# SH4_-_17V_BUCK_CONVERTER.net
KiCad netlist of a schematic drawn in Altium Designer
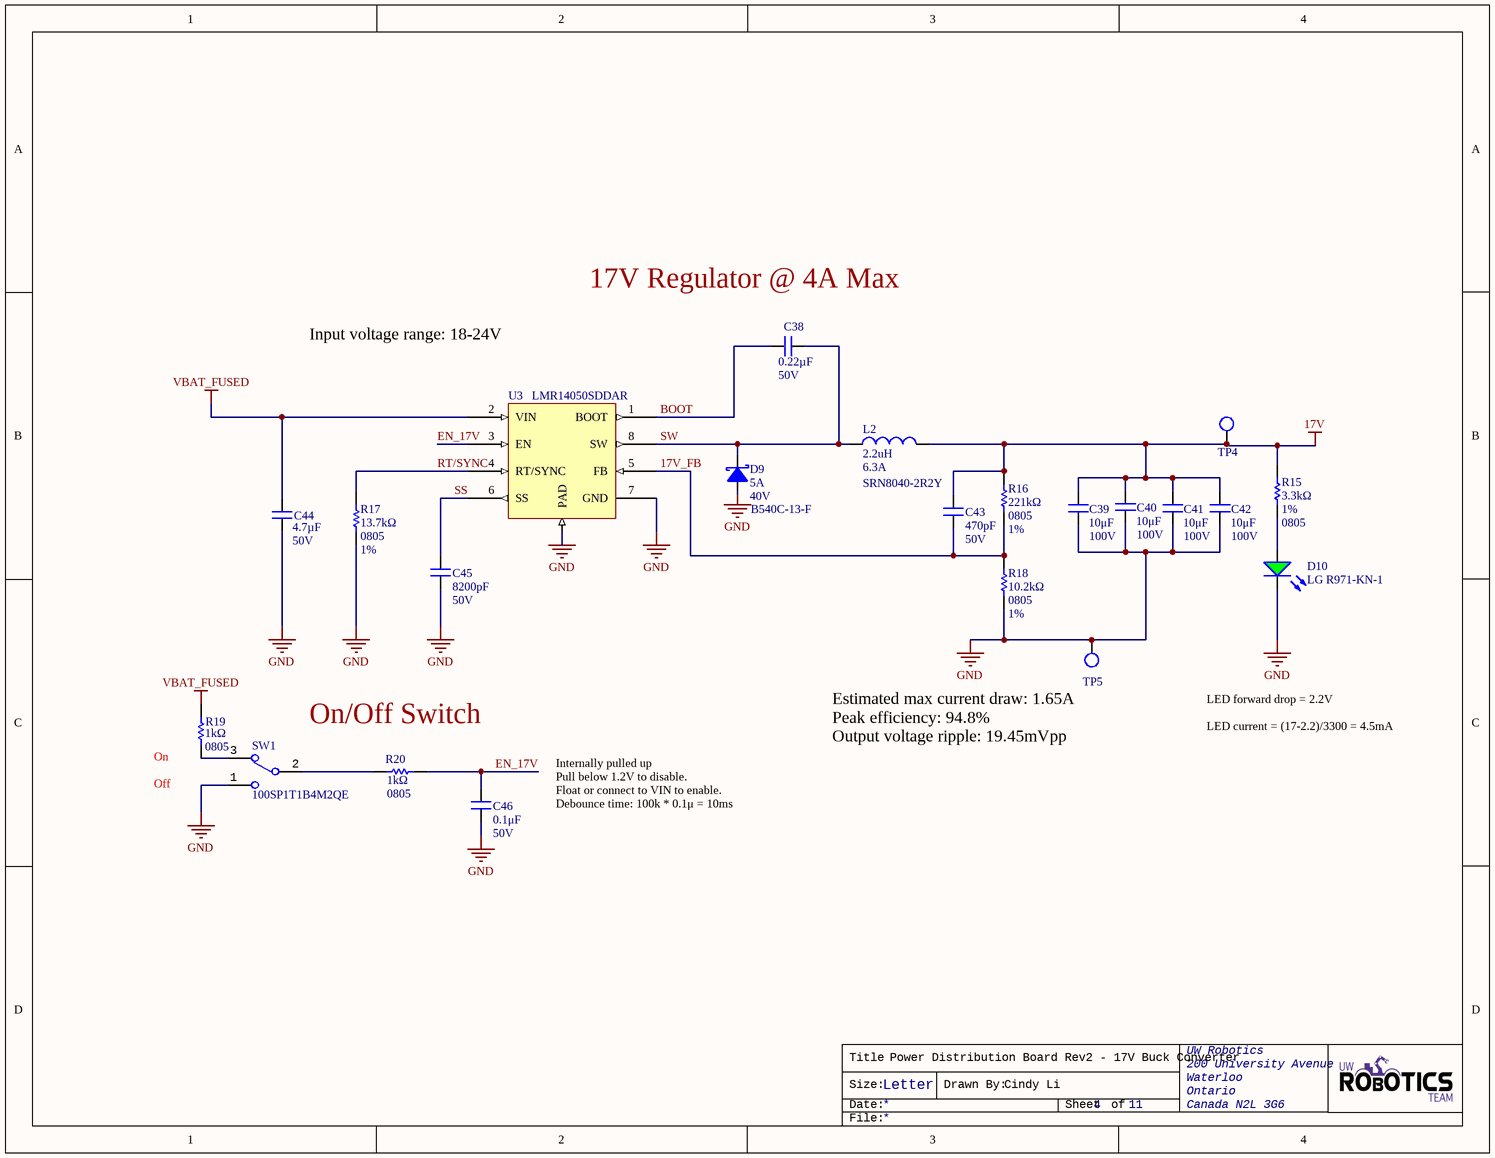
[diagram p0: SH4 - 17V BUCK CONVERTER.SchDoc]

(export (version "E")
  (design (tool "Eeschema 10.0.6"))
  (components
    (comp (ref "C38")
      (value "GRM21BR71H224MA01L")
      (footprint "CAP2012")
      (description "CAP CER 0.22UF 50V X7R 0805")
      (fields
        (field (name "TOLERANCE") "20%")
        (field (name "VOLTAGE RATING") "50V")
        (field (name "CAPACITANCE") "0.22µF")
      )
      (libsource (lib "UWRT_Schematic_Library_2020") (part "GRM21BR71H224MA01L"))
    )
    (comp (ref "C39")
      (value "10μF")
      (footprint "CAP1210")
      (description "CAP CER 10uF 100V X7S 10% 1210")
      (fields
        (field (name "TOLERANCE") "10%")
        (field (name "VOLTAGE RATING") "100V")
        (field (name "Comment") "CAP_10uF_100V_1210")
      )
      (libsource (lib "UWRT_Schematic_Library_2020") (part "CAP_10uF_100V_1210"))
    )
    (comp (ref "C40")
      (value "10μF")
      (footprint "CAP1210")
      (description "CAP CER 10uF 100V X7S 10% 1210")
      (fields
        (field (name "TOLERANCE") "10%")
        (field (name "VOLTAGE RATING") "100V")
        (field (name "Comment") "CAP_10uF_100V_1210")
      )
      (libsource (lib "UWRT_Schematic_Library_2020") (part "CAP_10uF_100V_1210"))
    )
    (comp (ref "C41")
      (value "10μF")
      (footprint "CAP1210")
      (description "CAP CER 10uF 100V X7S 10% 1210")
      (fields
        (field (name "TOLERANCE") "10%")
        (field (name "VOLTAGE RATING") "100V")
        (field (name "Comment") "CAP_10uF_100V_1210")
      )
      (libsource (lib "UWRT_Schematic_Library_2020") (part "CAP_10uF_100V_1210"))
    )
    (comp (ref "C42")
      (value "10μF")
      (footprint "CAP1210")
      (description "CAP CER 10uF 100V X7S 10% 1210")
      (fields
        (field (name "TOLERANCE") "10%")
        (field (name "VOLTAGE RATING") "100V")
        (field (name "Comment") "CAP_10uF_100V_1210")
      )
      (libsource (lib "UWRT_Schematic_Library_2020") (part "CAP_10uF_100V_1210"))
    )
    (comp (ref "C43")
      (value "470pF")
      (footprint "CAP2012")
      (description "CAP CER 470PF 50V X7R 0805")
      (fields (field (name "VOLTAGE RATING") "50V") (field (name "TOLERANCE") "5%"))
      (libsource (lib "UWRT_Schematic_Library_2020") (part "CAP_470pF_50V_0805"))
    )
    (comp (ref "C44")
      (value "GRM31CR71H475KA12L")
      (footprint "CAP1206")
      (description "CAP CER 4.7UF 50V X7R 1206")
      (fields
        (field (name "TOLERANCE") "10%")
        (field (name "VOLTAGE") "50V")
        (field (name "VOLTAGE RATING") "50V")
        (field (name "CAPACITANCE") "4.7µF")
      )
      (libsource (lib "UWRT_Schematic_Library_2020") (part "GRM31CR71H475KA12L"))
    )
    (comp (ref "C45")
      (value "8200pF")
      (footprint "CAP2012")
      (description "CAP CER 8200PF 50V X7R 0805")
      (fields (field (name "TOLERANCE") "10%") (field (name "VOLTAGE RATING") "50V"))
      (libsource (lib "UWRT_Schematic_Library_2020") (part "CAP_8200pF_50V_0805"))
    )
    (comp (ref "C46")
      (value "0.1μF")
      (footprint "CAP2012")
      (description "CAP CER 0.1UF 50V X7R 0805")
      (fields (field (name "VOLTAGE RATING") "50V") (field (name "TOLERANCE") "10%"))
      (libsource (lib "UWRT_Schematic_Library_2020") (part "CAP_0.1uF_50V_0805"))
    )
    (comp (ref "D9")
      (value "B540C-13-F")
      (footprint "DO214AB SMC")
      (description "DIODE SCHOTTKY 40V 5A SMC")
      (fields
        (field (name "MANUFACTURER PART NUMBER 1") "B540C-13-F")
        (field (name "FORWARD CURRENT") "5A")
        (field (name "VOLTAGE") "40V")
      )
      (libsource (lib "UWRT_Schematic_Library_2020") (part "B540C-13-F"))
    )
    (comp (ref "D10")
      (value "LG R971-KN-1")
      (footprint "LED_0805_GREEN")
      (description "LED GREEN DIFFUSED 0805 SMD")
      (libsource (lib "UWRT_Schematic_Library_2020") (part "DIO_LED_G"))
    )
    (comp (ref "L2")
      (value "SRN8040-2R2Y")
      (footprint "IND_BOURNS_SRN80")
      (description "FIXED IND 2.2UH 6.3A 13 MOHM SMD")
      (fields
        (field (name "MANUFACTURER PART NUMBER 1") "SRN8040-2R2Y")
        (field (name "TOLERANCE") "30%")
        (field (name "INDUCTANCE") "2.2uH")
        (field (name "MAX DC CURRENT") "6.3A")
      )
      (libsource (lib "UWRT_Schematic_Library_2020") (part "SRN8040-2R2Y"))
    )
    (comp (ref "R15")
      (value "3.3kΩ")
      (footprint "RESC2012X60N")
      (description "RES 3.3K OHM 1% 1/8W 0805")
      (fields (field (name "TOLERANCE") "1%") (field (name "CASE CODE (IMPERIAL)") "0805"))
      (libsource (lib "UWRT_Schematic_Library_2020") (part "RES_3.3kΩ_0805_1%"))
    )
    (comp (ref "R16")
      (value "221kΩ")
      (footprint "RESC2012X60N")
      (description "RES 221K OHM 1% 1/8W 0805")
      (fields (field (name "CASE CODE (IMPERIAL)") "0805") (field (name "TOLERANCE") "1%"))
      (libsource (lib "UWRT_Schematic_Library_2020") (part "RES_221kΩ_0805_1%"))
    )
    (comp (ref "R17")
      (value "13.7kΩ")
      (footprint "RESC2012X60N")
      (description "RES 13.7K OHM 1% 1/8W 0805")
      (fields (field (name "CASE CODE (IMPERIAL)") "0805") (field (name "TOLERANCE") "1%"))
      (libsource (lib "UWRT_Schematic_Library_2020") (part "RES_13.7kΩ_0805_1%"))
    )
    (comp (ref "R18")
      (value "10.2kΩ")
      (footprint "RESC2012X60N")
      (description "RES 10.2K OHM 1% 1/8W 0805")
      (fields (field (name "CASE CODE (IMPERIAL)") "0805") (field (name "TOLERANCE") "1%"))
      (libsource (lib "UWRT_Schematic_Library_2020") (part "RES_10.2kΩ_0805_1%"))
    )
    (comp (ref "R19")
      (value "1kΩ")
      (footprint "RESC2012X60N")
      (description "RES 1K OHM 1% 1/8W 0805")
      (fields (field (name "TOLERANCE") "1%") (field (name "CASE CODE (IMPERIAL)") "0805"))
      (libsource (lib "UWRT_Schematic_Library_2020") (part "RES_1kΩ_0805_1%"))
    )
    (comp (ref "R20")
      (value "1kΩ")
      (footprint "RESC2012X60N")
      (description "RES 1K OHM 1% 1/8W 0805")
      (fields (field (name "TOLERANCE") "1%") (field (name "CASE CODE (IMPERIAL)") "0805"))
      (libsource (lib "UWRT_Schematic_Library_2020") (part "RES_1kΩ_0805_1%"))
    )
    (comp (ref "SW1")
      (value "100SP1T1B4M2QE")
      (footprint "100SP1T1B4M2QE")
      (description "SWITCH TOGGLE SPDT 5A 120V")
      (libsource (lib "UWRT_Schematic_Library_2020") (part "SW_SPDT"))
    )
    (comp (ref "TP4")
      (value "TESTPOINT_LOOP")
      (footprint "TESTPOINT_LOOP")
      (description "PC TEST POINT MINIATURE WHITE")
      (libsource (lib "UWRT_Schematic_Library_2020") (part "TESTPOINT_LOOP"))
    )
    (comp (ref "TP5")
      (value "TESTPOINT_LOOP")
      (footprint "TESTPOINT_LOOP")
      (description "PC TEST POINT MINIATURE WHITE")
      (libsource (lib "UWRT_Schematic_Library_2020") (part "TESTPOINT_LOOP"))
    )
    (comp (ref "U3")
      (value "LMR14050SDDAR")
      (footprint "8-PowerSOIC")
      (description "IC REG BUCK ADJUSTABLE 5A 8SOPWR")
      (libsource (lib "UWRT_Schematic_Library_2020") (part "LMR14050SDDAR"))
    )
  )
  (nets
    (net (code "1") (name "/17V_FB") (class "Default")
      (node (ref "C43") (pin "1") (pinfunction "1_1") (pintype "passive"))
      (node (ref "R16") (pin "1") (pinfunction "1_1") (pintype "passive"))
      (node (ref "R18") (pin "2") (pinfunction "2_2") (pintype "passive"))
      (node (ref "U3") (pin "5") (pinfunction "FB_5") (pintype "input"))
    )
    (net (code "2") (name "/BOOT") (class "Default")
      (node (ref "C38") (pin "2") (pinfunction "2_2") (pintype "passive"))
      (node (ref "U3") (pin "1") (pinfunction "BOOT_1") (pintype "output"))
    )
    (net (code "3") (name "/EN_17V") (class "Default")
      (node (ref "C46") (pin "2") (pinfunction "2_2") (pintype "passive"))
      (node (ref "R20") (pin "2") (pinfunction "2_2") (pintype "passive"))
      (node (ref "U3") (pin "3") (pinfunction "EN_3") (pintype "input"))
    )
    (net (code "4") (name "/RT{slash}SYNC") (class "Default")
      (node (ref "R17") (pin "2") (pinfunction "2_2") (pintype "passive"))
      (node (ref "U3") (pin "4") (pinfunction "RT/SYNC_4") (pintype "input"))
    )
    (net (code "5") (name "/SS") (class "Default")
      (node (ref "C45") (pin "2") (pinfunction "2_2") (pintype "passive"))
      (node (ref "U3") (pin "6") (pinfunction "SS_6") (pintype "output"))
    )
    (net (code "6") (name "/SW") (class "Default")
      (node (ref "C38") (pin "1") (pinfunction "1_1") (pintype "passive"))
      (node (ref "D9") (pin "2") (pinfunction "Cathode_2") (pintype "passive"))
      (node (ref "L2") (pin "1") (pinfunction "1_1") (pintype "passive"))
      (node (ref "U3") (pin "8") (pinfunction "SW_8") (pintype "output"))
    )
    (net (code "7") (name "17V") (class "Default")
      (node (ref "C39") (pin "2") (pinfunction "2_2") (pintype "passive"))
      (node (ref "C40") (pin "2") (pinfunction "2_2") (pintype "passive"))
      (node (ref "C41") (pin "2") (pinfunction "2_2") (pintype "passive"))
      (node (ref "C42") (pin "2") (pinfunction "2_2") (pintype "passive"))
      (node (ref "C43") (pin "2") (pinfunction "2_2") (pintype "passive"))
      (node (ref "L2") (pin "2") (pinfunction "2_2") (pintype "passive"))
      (node (ref "R15") (pin "2") (pinfunction "2_2") (pintype "passive"))
      (node (ref "R16") (pin "2") (pinfunction "2_2") (pintype "passive"))
      (node (ref "TP4") (pin "1") (pintype "passive"))
    )
    (net (code "8") (name "GND") (class "Default")
      (node (ref "C39") (pin "1") (pinfunction "1_1") (pintype "passive"))
      (node (ref "C40") (pin "1") (pinfunction "1_1") (pintype "passive"))
      (node (ref "C41") (pin "1") (pinfunction "1_1") (pintype "passive"))
      (node (ref "C42") (pin "1") (pinfunction "1_1") (pintype "passive"))
      (node (ref "C44") (pin "2") (pinfunction "2_2") (pintype "passive"))
      (node (ref "C45") (pin "1") (pinfunction "1_1") (pintype "passive"))
      (node (ref "C46") (pin "1") (pinfunction "1_1") (pintype "passive"))
      (node (ref "D10") (pin "2") (pinfunction "K_2") (pintype "passive"))
      (node (ref "D9") (pin "1") (pinfunction "Anode_1") (pintype "passive"))
      (node (ref "R17") (pin "1") (pinfunction "1_1") (pintype "passive"))
      (node (ref "R18") (pin "1") (pinfunction "1_1") (pintype "passive"))
      (node (ref "SW1") (pin "1") (pinfunction "1_1") (pintype "passive"))
      (node (ref "TP5") (pin "1") (pintype "passive"))
      (node (ref "U3") (pin "7") (pinfunction "GND_7") (pintype "power_in"))
      (node (ref "U3") (pin "9") (pinfunction "PAD_9") (pintype "input"))
    )
    (net (code "9") (name "Net-(D10-A)") (class "Default")
      (node (ref "D10") (pin "1") (pinfunction "A_1") (pintype "passive"))
      (node (ref "R15") (pin "1") (pinfunction "1_1") (pintype "passive"))
    )
    (net (code "10") (name "Net-(R19-Pad1)") (class "Default")
      (node (ref "R19") (pin "1") (pinfunction "1_1") (pintype "passive"))
      (node (ref "SW1") (pin "3") (pinfunction "3_3") (pintype "passive"))
    )
    (net (code "11") (name "Net-(R20-Pad1)") (class "Default")
      (node (ref "R20") (pin "1") (pinfunction "1_1") (pintype "passive"))
      (node (ref "SW1") (pin "2") (pinfunction "2_2") (pintype "passive"))
    )
    (net (code "12") (name "VBAT_FUSED") (class "Default")
      (node (ref "C44") (pin "1") (pinfunction "1_1") (pintype "passive"))
      (node (ref "R19") (pin "2") (pinfunction "2_2") (pintype "passive"))
      (node (ref "U3") (pin "2") (pinfunction "VIN_2") (pintype "input"))
    )
  )
)
